# POWER.net
KiCad netlist of a schematic drawn in Altium Designer
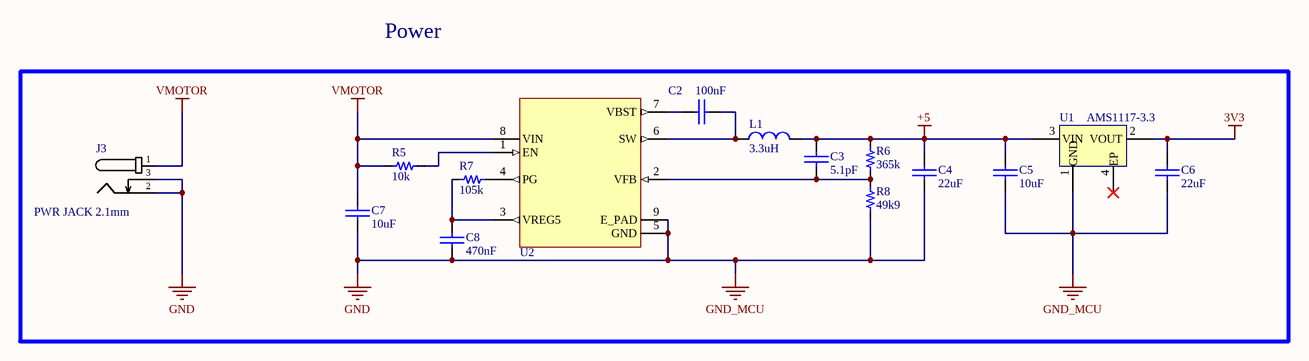
[diagram p0: POWER.SchDoc]

(export (version "E")
  (design (tool "Eeschema 10.0.6"))
  (components
    (comp (ref "C2")
      (value "100nF")
      (footprint "0603_cap")
      (description "50V 100nF X7R ±10% 0603 Ceramic Capacitors RoHS")
      (fields
        (field (name "MANUFACTURER") "FOJAN")
        (field (name "MANUFACTURER PART NUMBER") "FCC0603B104K500CT")
      )
      (libsource (lib "CNCLib") (part "Cap_100nF_0603_50V"))
    )
    (comp (ref "C3")
      (value "5.1pF")
      (footprint "0603_cap")
      (description "50V 5.1pF NP0 0603 Ceramic Capacitors RoHS")
      (fields
        (field (name "MANUFACTURER") "YAGEO")
        (field (name "MANUFACTURER PART NUMBER") "CC0603CRNPO9BN5R1")
      )
      (libsource (lib "CNCLib") (part "Cap_5.1pF"))
    )
    (comp (ref "C4")
      (value "22uF")
      (footprint "0603_cap")
      (description "10V 22uF X5R ±20% 0603 Multilayer Ceramic Capacitors MLCC - SMD/SMT ROHS")
      (fields
        (field (name "MANUFACTURER") "HRE")
        (field (name "MANUFACTURER PART NUMBER") "CGA0603X5R226M100JT")
      )
      (libsource (lib "CNCLib") (part "Cap_22uF_0603_10V"))
    )
    (comp (ref "C5")
      (value "10uF")
      (footprint "0603_cap")
      (description "10V 10uF X5R ±10% 0603 Multilayer Ceramic Capacitors MLCC - SMD/SMT ROHS")
      (fields
        (field (name "MANUFACTURER") "CCTC")
        (field (name "MANUFACTURER PART NUMBER") "TCC0603X5R106K100CT")
      )
      (libsource (lib "CNCLib") (part "Cap_10uF_0603_10V"))
    )
    (comp (ref "C6")
      (value "22uF")
      (footprint "0603_cap")
      (description "10V 22uF X5R ±20% 0603 Multilayer Ceramic Capacitors MLCC - SMD/SMT ROHS")
      (fields
        (field (name "MANUFACTURER") "HRE")
        (field (name "MANUFACTURER PART NUMBER") "CGA0603X5R226M100JT")
      )
      (libsource (lib "CNCLib") (part "Cap_22uF_0603_10V"))
    )
    (comp (ref "C7")
      (value "10uF")
      (footprint "0805_cap")
      (description "25V 10uF X5R ±10% 0805 Multilayer Ceramic Capacitors MLCC - SMD/SMT ROHS")
      (fields
        (field (name "MANUFACTURER") "Samsung Electro-Mechanics")
        (field (name "MANUFACTURER PART NUMBER") "CL21A106KAYNNNE")
      )
      (libsource (lib "CNCLib") (part "Cap_10uF_0805_25V_"))
    )
    (comp (ref "C8")
      (value "470nF")
      (footprint "0603_cap")
      (description "50V 470nF X7R ±10% 0603 Multilayer Ceramic Capacitors MLCC - SMD/SMT ROHS")
      (fields
        (field (name "MANUFACTURER") "Chinocera")
        (field (name "MANUFACTURER PART NUMBER") "HGC0603R7474K500NTHJ")
      )
      (libsource (lib "CNCLib") (part "Cap_470nF_0603_50V"))
    )
    (comp (ref "J3")
      (value "PWR JACK 2.1mm")
      (footprint "CON_POWER_BARREL_2.1MM_3CONN")
      (description "CONN PWR JACK 2X5.5MM SOLDER")
      (fields (field (name "MANUFACTURER") "HCTL") (field (name "MANUFACTURER PART NUMBER") "HC-DC-005-2.0T"))
      (libsource (lib "CNCLib") (part "Con_Power_Jack_2.1mm_3pins"))
    )
    (comp (ref "L1")
      (value "3.3uH")
      (footprint "Inductor_3_3uH")
      (description "2.6A 3.3uH Magnetic Shielded Inductor ±20% 3.6A 52mΩ SMD,4x4mm Fixed Inductors RoHS")
      (fields
        (field (name "MANUFACTURER") "cjiang")
        (field (name "MANUFACTURER PART NUMBER") "FNR4030S3R3MT")
      )
      (libsource (lib "CNCLib") (part "Inductor_3.3uH"))
    )
    (comp (ref "R5")
      (value "10k")
      (footprint "0603_res")
      (description "RES SMD 10k OHM 5% 1/10W 0603")
      (fields (field (name "MANUFACTURER") "FOJAN") (field (name "MANUFACTURER PART NUMBER") "FRC0603J103TS"))
      (libsource (lib "CNCLib") (part "Res_10k_0603_1/10W"))
    )
    (comp (ref "R6")
      (value "365k")
      (footprint "0603_res")
      (description "100mW Thick Film Resistor 75V ±100ppm/℃ ±1% 365kΩ 0603 Chip Resistor - Surface Mount ROHS")
      (fields
        (field (name "MANUFACTURER") "YAGEO")
        (field (name "MANUFACTURER PART NUMBER") "RC0603FR-07365KL")
      )
      (libsource (lib "CNCLib") (part "Res_365k_0603_1/10W"))
    )
    (comp (ref "R7")
      (value "105k")
      (footprint "0603_res")
      (description "100mW 105kΩ 75V ±25ppm/℃ Thin Film Resistor ±0.5% 0603 Chip Resistor - Surface Mount RoHS")
      (fields
        (field (name "MANUFACTURER") "YAGEO")
        (field (name "MANUFACTURER PART NUMBER") "RT0603DRD07105KL")
      )
      (libsource (lib "CNCLib") (part "Res 105k"))
    )
    (comp (ref "R8")
      (value "49k9")
      (footprint "0603_res")
      (description "100mW Thick Film Resistor 75V ±100ppm/℃ ±1% 49.9kΩ 0603 Chip Resistor - Surface Mount ROHS")
      (fields
        (field (name "MANUFACTURER") "YAGEO")
        (field (name "MANUFACTURER PART NUMBER") "RC0603FR-0749K9L")
      )
      (libsource (lib "CNCLib") (part "Res_49k9_0603_1/10W"))
    )
    (comp (ref "U1")
      (value "AMS1117-3.3")
      (footprint "SOT_223")
      (description "1A 60dB@(120Hz) Fixed 3.3V Positive 18V SOT-223 Linear Voltage Regulators (LDO) ROHS")
      (fields (field (name "MANUFACTURER") "UMW(Youtai Semiconductor Co., Ltd.)"))
      (libsource (lib "CNCLib") (part "LDO_3V3_1A_FIXED"))
    )
    (comp (ref "U2")
      (value "TPS56528DDAR")
      (footprint "SOIC_8_3.9mm_EP")
      (description "IC REG BUCK ADJ 5A 8SOPWR")
      (fields (field (name "MANUFACTURER") "Texas Instruments"))
      (libsource (lib "CNCLib") (part "DCDC_SW_BUCK_5A_SOIC8"))
    )
  )
  (nets
    (net (code "1") (name "+5") (class "Default")
      (node (ref "C3") (pin "1") (pinfunction "1_1") (pintype "passive"))
      (node (ref "C4") (pin "1") (pinfunction "1_1") (pintype "passive"))
      (node (ref "C5") (pin "1") (pinfunction "1_1") (pintype "passive"))
      (node (ref "L1") (pin "2") (pinfunction "2_2") (pintype "passive"))
      (node (ref "R6") (pin "2") (pinfunction "2_2") (pintype "passive"))
      (node (ref "U1") (pin "3") (pinfunction "VIN_3") (pintype "passive"))
    )
    (net (code "2") (name "3V3") (class "Default")
      (node (ref "C6") (pin "1") (pinfunction "1_1") (pintype "passive"))
      (node (ref "U1") (pin "2") (pinfunction "VOUT_2") (pintype "passive"))
    )
    (net (code "3") (name "GND") (class "Default")
      (node (ref "C4") (pin "2") (pinfunction "2_2") (pintype "passive"))
      (node (ref "C5") (pin "2") (pinfunction "2_2") (pintype "passive"))
      (node (ref "C6") (pin "2") (pinfunction "2_2") (pintype "passive"))
      (node (ref "C7") (pin "2") (pinfunction "2_2") (pintype "passive"))
      (node (ref "C8") (pin "2") (pinfunction "2_2") (pintype "passive"))
      (node (ref "J3") (pin "2") (pinfunction "2_2") (pintype "passive"))
      (node (ref "J3") (pin "3") (pinfunction "3_3") (pintype "passive"))
      (node (ref "R8") (pin "1") (pinfunction "1_1") (pintype "passive"))
      (node (ref "U1") (pin "1") (pinfunction "GND_1") (pintype "passive"))
      (node (ref "U2") (pin "5") (pinfunction "GND_5") (pintype "power_in"))
      (node (ref "U2") (pin "9") (pinfunction "E_PAD_9") (pintype "power_in"))
    )
    (net (code "4") (name "Net-(U2-EN)") (class "Default")
      (node (ref "R5") (pin "2") (pinfunction "2_2") (pintype "passive"))
      (node (ref "U2") (pin "1") (pinfunction "EN_1") (pintype "input"))
    )
    (net (code "5") (name "Net-(U2-PG)") (class "Default")
      (node (ref "R7") (pin "2") (pinfunction "2_2") (pintype "passive"))
      (node (ref "U2") (pin "4") (pinfunction "PG_4") (pintype "output"))
    )
    (net (code "6") (name "Net-(U2-SW)") (class "Default")
      (node (ref "C2") (pin "1") (pinfunction "1_1") (pintype "passive"))
      (node (ref "L1") (pin "1") (pinfunction "1_1") (pintype "passive"))
      (node (ref "U2") (pin "6") (pinfunction "SW_6") (pintype "output"))
    )
    (net (code "7") (name "Net-(U2-VBST)") (class "Default")
      (node (ref "C2") (pin "2") (pinfunction "2_2") (pintype "passive"))
      (node (ref "U2") (pin "7") (pinfunction "VBST_7") (pintype "output"))
    )
    (net (code "8") (name "Net-(U2-VFB)") (class "Default")
      (node (ref "C3") (pin "2") (pinfunction "2_2") (pintype "passive"))
      (node (ref "R6") (pin "1") (pinfunction "1_1") (pintype "passive"))
      (node (ref "R8") (pin "2") (pinfunction "2_2") (pintype "passive"))
      (node (ref "U2") (pin "2") (pinfunction "VFB_2") (pintype "input"))
    )
    (net (code "9") (name "Net-(U2-VREG5)") (class "Default")
      (node (ref "C8") (pin "1") (pinfunction "1_1") (pintype "passive"))
      (node (ref "R7") (pin "1") (pinfunction "1_1") (pintype "passive"))
      (node (ref "U2") (pin "3") (pinfunction "VREG5_3") (pintype "output"))
    )
    (net (code "10") (name "VMOTOR") (class "Default")
      (node (ref "C7") (pin "1") (pinfunction "1_1") (pintype "passive"))
      (node (ref "J3") (pin "1") (pinfunction "1_1") (pintype "passive"))
      (node (ref "R5") (pin "1") (pinfunction "1_1") (pintype "passive"))
      (node (ref "U2") (pin "8") (pinfunction "VIN_8") (pintype "power_in"))
    )
    (net (code "11") (name "unconnected-(U1-EP-Pad4)") (class "Default")
      (node (ref "U1") (pin "4") (pinfunction "EP_4") (pintype "passive+no_connect"))
    )
  )
)
